# vbat_board.net
KiCad netlist of a schematic drawn in EAGLE
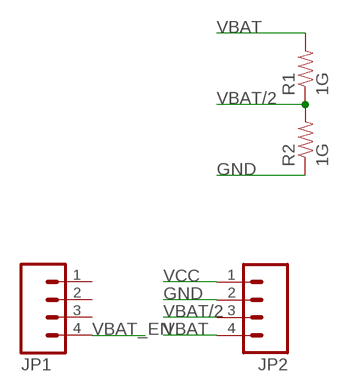
[diagram p0: schematic, sheet 1]

(export (version "E")
  (design (tool "Eeschema 10.0.6"))
  (components
    (comp (ref "JP1")
      (value "M04PTH")
      (footprint "eagle-import:1X04")
      (libsource (lib "eagle-import") (part "M04PTH"))
    )
    (comp (ref "JP2")
      (value "M04PTH")
      (footprint "eagle-import:1X04")
      (libsource (lib "eagle-import") (part "M04PTH"))
    )
    (comp (ref "R1")
      (value "1G")
      (footprint "eagle-import:TH_0.3-RES")
      (libsource (lib "eagle-import") (part "RESISTORAXIAL-0.3"))
    )
    (comp (ref "R2")
      (value "1G")
      (footprint "eagle-import:TH_0.3-RES")
      (libsource (lib "eagle-import") (part "RESISTORAXIAL-0.3"))
    )
  )
  (nets
    (net (code "1") (name "/GND") (class "Default")
      (node (ref "JP2") (pin "2") (pinfunction "2_2") (pintype "passive"))
      (node (ref "R2") (pin "P$1") (pinfunction "1_P$1") (pintype "passive"))
    )
    (net (code "2") (name "/VBAT") (class "Default")
      (node (ref "JP2") (pin "4") (pinfunction "4_4") (pintype "passive"))
      (node (ref "R1") (pin "P$2") (pinfunction "2_P$2") (pintype "passive"))
    )
    (net (code "3") (name "/VBAT_EN") (class "Default")
      (node (ref "JP1") (pin "4") (pinfunction "4_4") (pintype "passive"))
    )
    (net (code "4") (name "/VBAT{slash}2") (class "Default")
      (node (ref "JP2") (pin "3") (pinfunction "3_3") (pintype "passive"))
      (node (ref "R1") (pin "P$1") (pinfunction "1_P$1") (pintype "passive"))
      (node (ref "R2") (pin "P$2") (pinfunction "2_P$2") (pintype "passive"))
    )
    (net (code "5") (name "/VCC") (class "Default")
      (node (ref "JP2") (pin "1") (pinfunction "1_1") (pintype "passive"))
    )
    (net (code "6") (name "unconnected-(JP1-Pad1)") (class "Default")
      (node (ref "JP1") (pin "1") (pinfunction "1_1") (pintype "passive"))
    )
    (net (code "7") (name "unconnected-(JP1-Pad2)") (class "Default")
      (node (ref "JP1") (pin "2") (pinfunction "2_2") (pintype "passive"))
    )
    (net (code "8") (name "unconnected-(JP1-Pad3)") (class "Default")
      (node (ref "JP1") (pin "3") (pinfunction "3_3") (pintype "passive"))
    )
  )
)
